# ws2803_top.net
KiCad netlist of a schematic drawn in EAGLE
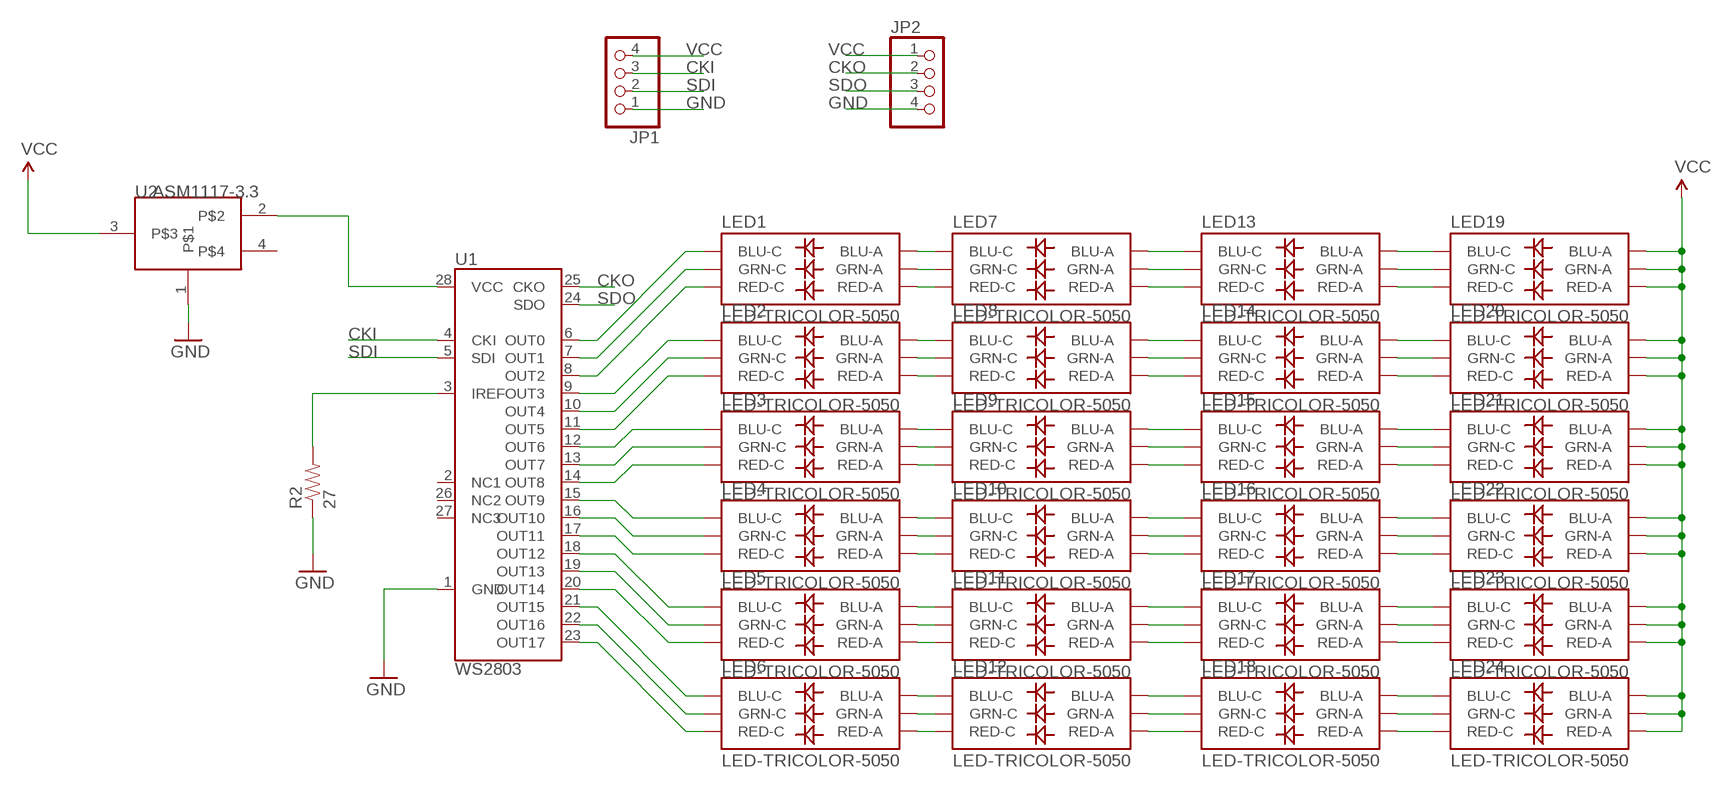
[diagram p0: schematic, sheet 1]

(export (version "E")
  (design (tool "Eeschema 10.0.6"))
  (components
    (comp (ref "JP1")
      (value "PINHD-1X4")
      (footprint "eagle-import:1X04")
      (libsource (lib "eagle-import") (part "PINHD-1X4"))
    )
    (comp (ref "JP2")
      (value "PINHD-1X4")
      (footprint "eagle-import:1X04")
      (libsource (lib "eagle-import") (part "PINHD-1X4"))
    )
    (comp (ref "LED1")
      (value "LED-TRICOLOR-5050")
      (footprint "eagle-import:LED-TRICOLOR-5050")
      (libsource (lib "eagle-import") (part "LED-TRICOLOR-5050"))
    )
    (comp (ref "LED2")
      (value "LED-TRICOLOR-5050")
      (footprint "eagle-import:LED-TRICOLOR-5050")
      (libsource (lib "eagle-import") (part "LED-TRICOLOR-5050"))
    )
    (comp (ref "LED3")
      (value "LED-TRICOLOR-5050")
      (footprint "eagle-import:LED-TRICOLOR-5050")
      (libsource (lib "eagle-import") (part "LED-TRICOLOR-5050"))
    )
    (comp (ref "LED4")
      (value "LED-TRICOLOR-5050")
      (footprint "eagle-import:LED-TRICOLOR-5050")
      (libsource (lib "eagle-import") (part "LED-TRICOLOR-5050"))
    )
    (comp (ref "LED5")
      (value "LED-TRICOLOR-5050")
      (footprint "eagle-import:LED-TRICOLOR-5050")
      (libsource (lib "eagle-import") (part "LED-TRICOLOR-5050"))
    )
    (comp (ref "LED6")
      (value "LED-TRICOLOR-5050")
      (footprint "eagle-import:LED-TRICOLOR-5050")
      (libsource (lib "eagle-import") (part "LED-TRICOLOR-5050"))
    )
    (comp (ref "LED7")
      (value "LED-TRICOLOR-5050")
      (footprint "eagle-import:LED-TRICOLOR-5050")
      (libsource (lib "eagle-import") (part "LED-TRICOLOR-5050"))
    )
    (comp (ref "LED8")
      (value "LED-TRICOLOR-5050")
      (footprint "eagle-import:LED-TRICOLOR-5050")
      (libsource (lib "eagle-import") (part "LED-TRICOLOR-5050"))
    )
    (comp (ref "LED9")
      (value "LED-TRICOLOR-5050")
      (footprint "eagle-import:LED-TRICOLOR-5050")
      (libsource (lib "eagle-import") (part "LED-TRICOLOR-5050"))
    )
    (comp (ref "LED10")
      (value "LED-TRICOLOR-5050")
      (footprint "eagle-import:LED-TRICOLOR-5050")
      (libsource (lib "eagle-import") (part "LED-TRICOLOR-5050"))
    )
    (comp (ref "LED11")
      (value "LED-TRICOLOR-5050")
      (footprint "eagle-import:LED-TRICOLOR-5050")
      (libsource (lib "eagle-import") (part "LED-TRICOLOR-5050"))
    )
    (comp (ref "LED12")
      (value "LED-TRICOLOR-5050")
      (footprint "eagle-import:LED-TRICOLOR-5050")
      (libsource (lib "eagle-import") (part "LED-TRICOLOR-5050"))
    )
    (comp (ref "LED13")
      (value "LED-TRICOLOR-5050")
      (footprint "eagle-import:LED-TRICOLOR-5050")
      (libsource (lib "eagle-import") (part "LED-TRICOLOR-5050"))
    )
    (comp (ref "LED14")
      (value "LED-TRICOLOR-5050")
      (footprint "eagle-import:LED-TRICOLOR-5050")
      (libsource (lib "eagle-import") (part "LED-TRICOLOR-5050"))
    )
    (comp (ref "LED15")
      (value "LED-TRICOLOR-5050")
      (footprint "eagle-import:LED-TRICOLOR-5050")
      (libsource (lib "eagle-import") (part "LED-TRICOLOR-5050"))
    )
    (comp (ref "LED16")
      (value "LED-TRICOLOR-5050")
      (footprint "eagle-import:LED-TRICOLOR-5050")
      (libsource (lib "eagle-import") (part "LED-TRICOLOR-5050"))
    )
    (comp (ref "LED17")
      (value "LED-TRICOLOR-5050")
      (footprint "eagle-import:LED-TRICOLOR-5050")
      (libsource (lib "eagle-import") (part "LED-TRICOLOR-5050"))
    )
    (comp (ref "LED18")
      (value "LED-TRICOLOR-5050")
      (footprint "eagle-import:LED-TRICOLOR-5050")
      (libsource (lib "eagle-import") (part "LED-TRICOLOR-5050"))
    )
    (comp (ref "LED19")
      (value "LED-TRICOLOR-5050")
      (footprint "eagle-import:LED-TRICOLOR-5050")
      (libsource (lib "eagle-import") (part "LED-TRICOLOR-5050"))
    )
    (comp (ref "LED20")
      (value "LED-TRICOLOR-5050")
      (footprint "eagle-import:LED-TRICOLOR-5050")
      (libsource (lib "eagle-import") (part "LED-TRICOLOR-5050"))
    )
    (comp (ref "LED21")
      (value "LED-TRICOLOR-5050")
      (footprint "eagle-import:LED-TRICOLOR-5050")
      (libsource (lib "eagle-import") (part "LED-TRICOLOR-5050"))
    )
    (comp (ref "LED22")
      (value "LED-TRICOLOR-5050")
      (footprint "eagle-import:LED-TRICOLOR-5050")
      (libsource (lib "eagle-import") (part "LED-TRICOLOR-5050"))
    )
    (comp (ref "LED23")
      (value "LED-TRICOLOR-5050")
      (footprint "eagle-import:LED-TRICOLOR-5050")
      (libsource (lib "eagle-import") (part "LED-TRICOLOR-5050"))
    )
    (comp (ref "LED24")
      (value "LED-TRICOLOR-5050")
      (footprint "eagle-import:LED-TRICOLOR-5050")
      (libsource (lib "eagle-import") (part "LED-TRICOLOR-5050"))
    )
    (comp (ref "R2")
      (value "27")
      (footprint "eagle-import:0603-RES")
      (libsource (lib "eagle-import") (part "RESISTOR0603-RES"))
    )
    (comp (ref "U1")
      (value "WS2803")
      (footprint "eagle-import:SOP-28")
      (libsource (lib "eagle-import") (part "WS2803"))
    )
    (comp (ref "U2")
      (value "ASM1117-3.3")
      (footprint "eagle-import:SOT223")
      (libsource (lib "eagle-import") (part "ASM1117-3.3"))
    )
  )
  (nets
    (net (code "1") (name "/CKI") (class "Default")
      (node (ref "JP1") (pin "3") (pinfunction "3_3") (pintype "passive"))
      (node (ref "U1") (pin "4") (pinfunction "CKI_4") (pintype "bidirectional"))
    )
    (net (code "2") (name "/CKO") (class "Default")
      (node (ref "JP2") (pin "2") (pinfunction "2_2") (pintype "passive"))
      (node (ref "U1") (pin "25") (pinfunction "CKO_25") (pintype "bidirectional"))
    )
    (net (code "3") (name "/SDI") (class "Default")
      (node (ref "JP1") (pin "2") (pinfunction "2_2") (pintype "passive"))
      (node (ref "U1") (pin "5") (pinfunction "SDI_5") (pintype "bidirectional"))
    )
    (net (code "4") (name "/SDO") (class "Default")
      (node (ref "JP2") (pin "3") (pinfunction "3_3") (pintype "passive"))
      (node (ref "U1") (pin "24") (pinfunction "SDO_24") (pintype "bidirectional"))
    )
    (net (code "5") (name "GND") (class "Default")
      (node (ref "JP1") (pin "1") (pinfunction "1_1") (pintype "passive"))
      (node (ref "JP2") (pin "4") (pinfunction "4_4") (pintype "passive"))
      (node (ref "R2") (pin "1") (pinfunction "1_1") (pintype "passive"))
      (node (ref "U1") (pin "1") (pinfunction "GND_1") (pintype "bidirectional"))
      (node (ref "U2") (pin "1") (pinfunction "P$1_1") (pintype "bidirectional"))
    )
    (net (code "6") (name "Net-(LED1-BLU-A)") (class "Default")
      (node (ref "LED1") (pin "3") (pinfunction "BLU-A_3") (pintype "bidirectional"))
      (node (ref "LED7") (pin "4") (pinfunction "BLU-C_4") (pintype "bidirectional"))
    )
    (net (code "7") (name "Net-(LED1-BLU-C)") (class "Default")
      (node (ref "LED1") (pin "4") (pinfunction "BLU-C_4") (pintype "bidirectional"))
      (node (ref "U1") (pin "6") (pinfunction "OUT0_6") (pintype "bidirectional"))
    )
    (net (code "8") (name "Net-(LED1-GRN-A)") (class "Default")
      (node (ref "LED1") (pin "1") (pinfunction "GRN-A_1") (pintype "bidirectional"))
      (node (ref "LED7") (pin "6") (pinfunction "GRN-C_6") (pintype "bidirectional"))
    )
    (net (code "9") (name "Net-(LED1-GRN-C)") (class "Default")
      (node (ref "LED1") (pin "6") (pinfunction "GRN-C_6") (pintype "bidirectional"))
      (node (ref "U1") (pin "7") (pinfunction "OUT1_7") (pintype "bidirectional"))
    )
    (net (code "10") (name "Net-(LED1-RED-A)") (class "Default")
      (node (ref "LED1") (pin "2") (pinfunction "RED-A_2") (pintype "bidirectional"))
      (node (ref "LED7") (pin "5") (pinfunction "RED-C_5") (pintype "bidirectional"))
    )
    (net (code "11") (name "Net-(LED1-RED-C)") (class "Default")
      (node (ref "LED1") (pin "5") (pinfunction "RED-C_5") (pintype "bidirectional"))
      (node (ref "U1") (pin "8") (pinfunction "OUT2_8") (pintype "bidirectional"))
    )
    (net (code "12") (name "Net-(LED2-BLU-A)") (class "Default")
      (node (ref "LED2") (pin "3") (pinfunction "BLU-A_3") (pintype "bidirectional"))
      (node (ref "LED8") (pin "4") (pinfunction "BLU-C_4") (pintype "bidirectional"))
    )
    (net (code "13") (name "Net-(LED2-BLU-C)") (class "Default")
      (node (ref "LED2") (pin "4") (pinfunction "BLU-C_4") (pintype "bidirectional"))
      (node (ref "U1") (pin "9") (pinfunction "OUT3_9") (pintype "bidirectional"))
    )
    (net (code "14") (name "Net-(LED2-GRN-A)") (class "Default")
      (node (ref "LED2") (pin "1") (pinfunction "GRN-A_1") (pintype "bidirectional"))
      (node (ref "LED8") (pin "6") (pinfunction "GRN-C_6") (pintype "bidirectional"))
    )
    (net (code "15") (name "Net-(LED2-GRN-C)") (class "Default")
      (node (ref "LED2") (pin "6") (pinfunction "GRN-C_6") (pintype "bidirectional"))
      (node (ref "U1") (pin "10") (pinfunction "OUT4_10") (pintype "bidirectional"))
    )
    (net (code "16") (name "Net-(LED2-RED-A)") (class "Default")
      (node (ref "LED2") (pin "2") (pinfunction "RED-A_2") (pintype "bidirectional"))
      (node (ref "LED8") (pin "5") (pinfunction "RED-C_5") (pintype "bidirectional"))
    )
    (net (code "17") (name "Net-(LED2-RED-C)") (class "Default")
      (node (ref "LED2") (pin "5") (pinfunction "RED-C_5") (pintype "bidirectional"))
      (node (ref "U1") (pin "11") (pinfunction "OUT5_11") (pintype "bidirectional"))
    )
    (net (code "18") (name "Net-(LED3-BLU-A)") (class "Default")
      (node (ref "LED3") (pin "3") (pinfunction "BLU-A_3") (pintype "bidirectional"))
      (node (ref "LED9") (pin "4") (pinfunction "BLU-C_4") (pintype "bidirectional"))
    )
    (net (code "19") (name "Net-(LED3-BLU-C)") (class "Default")
      (node (ref "LED3") (pin "4") (pinfunction "BLU-C_4") (pintype "bidirectional"))
      (node (ref "U1") (pin "12") (pinfunction "OUT6_12") (pintype "bidirectional"))
    )
    (net (code "20") (name "Net-(LED3-GRN-A)") (class "Default")
      (node (ref "LED3") (pin "1") (pinfunction "GRN-A_1") (pintype "bidirectional"))
      (node (ref "LED9") (pin "6") (pinfunction "GRN-C_6") (pintype "bidirectional"))
    )
    (net (code "21") (name "Net-(LED3-GRN-C)") (class "Default")
      (node (ref "LED3") (pin "6") (pinfunction "GRN-C_6") (pintype "bidirectional"))
      (node (ref "U1") (pin "13") (pinfunction "OUT7_13") (pintype "bidirectional"))
    )
    (net (code "22") (name "Net-(LED3-RED-A)") (class "Default")
      (node (ref "LED3") (pin "2") (pinfunction "RED-A_2") (pintype "bidirectional"))
      (node (ref "LED9") (pin "5") (pinfunction "RED-C_5") (pintype "bidirectional"))
    )
    (net (code "23") (name "Net-(LED3-RED-C)") (class "Default")
      (node (ref "LED3") (pin "5") (pinfunction "RED-C_5") (pintype "bidirectional"))
      (node (ref "U1") (pin "14") (pinfunction "OUT8_14") (pintype "bidirectional"))
    )
    (net (code "24") (name "Net-(LED4-BLU-C)") (class "Default")
      (node (ref "LED4") (pin "4") (pinfunction "BLU-C_4") (pintype "bidirectional"))
      (node (ref "U1") (pin "15") (pinfunction "OUT9_15") (pintype "bidirectional"))
    )
    (net (code "25") (name "Net-(LED4-GRN-C)") (class "Default")
      (node (ref "LED4") (pin "6") (pinfunction "GRN-C_6") (pintype "bidirectional"))
      (node (ref "U1") (pin "16") (pinfunction "OUT10_16") (pintype "bidirectional"))
    )
    (net (code "26") (name "Net-(LED4-RED-C)") (class "Default")
      (node (ref "LED4") (pin "5") (pinfunction "RED-C_5") (pintype "bidirectional"))
      (node (ref "U1") (pin "17") (pinfunction "OUT11_17") (pintype "bidirectional"))
    )
    (net (code "27") (name "Net-(LED5-BLU-C)") (class "Default")
      (node (ref "LED5") (pin "4") (pinfunction "BLU-C_4") (pintype "bidirectional"))
      (node (ref "U1") (pin "18") (pinfunction "OUT12_18") (pintype "bidirectional"))
    )
    (net (code "28") (name "Net-(LED5-GRN-C)") (class "Default")
      (node (ref "LED5") (pin "6") (pinfunction "GRN-C_6") (pintype "bidirectional"))
      (node (ref "U1") (pin "19") (pinfunction "OUT13_19") (pintype "bidirectional"))
    )
    (net (code "29") (name "Net-(LED5-RED-C)") (class "Default")
      (node (ref "LED5") (pin "5") (pinfunction "RED-C_5") (pintype "bidirectional"))
      (node (ref "U1") (pin "20") (pinfunction "OUT14_20") (pintype "bidirectional"))
    )
    (net (code "30") (name "Net-(LED6-BLU-C)") (class "Default")
      (node (ref "LED6") (pin "4") (pinfunction "BLU-C_4") (pintype "bidirectional"))
      (node (ref "U1") (pin "21") (pinfunction "OUT15_21") (pintype "bidirectional"))
    )
    (net (code "31") (name "Net-(LED6-GRN-C)") (class "Default")
      (node (ref "LED6") (pin "6") (pinfunction "GRN-C_6") (pintype "bidirectional"))
      (node (ref "U1") (pin "22") (pinfunction "OUT16_22") (pintype "bidirectional"))
    )
    (net (code "32") (name "Net-(LED6-RED-C)") (class "Default")
      (node (ref "LED6") (pin "5") (pinfunction "RED-C_5") (pintype "bidirectional"))
      (node (ref "U1") (pin "23") (pinfunction "OUT17_23") (pintype "bidirectional"))
    )
    (net (code "33") (name "Net-(LED10-BLU-A)") (class "Default")
      (node (ref "LED10") (pin "3") (pinfunction "BLU-A_3") (pintype "bidirectional"))
      (node (ref "LED16") (pin "4") (pinfunction "BLU-C_4") (pintype "bidirectional"))
    )
    (net (code "34") (name "Net-(LED10-BLU-C)") (class "Default")
      (node (ref "LED10") (pin "4") (pinfunction "BLU-C_4") (pintype "bidirectional"))
      (node (ref "LED4") (pin "3") (pinfunction "BLU-A_3") (pintype "bidirectional"))
    )
    (net (code "35") (name "Net-(LED10-GRN-A)") (class "Default")
      (node (ref "LED10") (pin "1") (pinfunction "GRN-A_1") (pintype "bidirectional"))
      (node (ref "LED16") (pin "6") (pinfunction "GRN-C_6") (pintype "bidirectional"))
    )
    (net (code "36") (name "Net-(LED10-GRN-C)") (class "Default")
      (node (ref "LED10") (pin "6") (pinfunction "GRN-C_6") (pintype "bidirectional"))
      (node (ref "LED4") (pin "1") (pinfunction "GRN-A_1") (pintype "bidirectional"))
    )
    (net (code "37") (name "Net-(LED10-RED-A)") (class "Default")
      (node (ref "LED10") (pin "2") (pinfunction "RED-A_2") (pintype "bidirectional"))
      (node (ref "LED16") (pin "5") (pinfunction "RED-C_5") (pintype "bidirectional"))
    )
    (net (code "38") (name "Net-(LED10-RED-C)") (class "Default")
      (node (ref "LED10") (pin "5") (pinfunction "RED-C_5") (pintype "bidirectional"))
      (node (ref "LED4") (pin "2") (pinfunction "RED-A_2") (pintype "bidirectional"))
    )
    (net (code "39") (name "Net-(LED11-BLU-A)") (class "Default")
      (node (ref "LED11") (pin "3") (pinfunction "BLU-A_3") (pintype "bidirectional"))
      (node (ref "LED17") (pin "4") (pinfunction "BLU-C_4") (pintype "bidirectional"))
    )
    (net (code "40") (name "Net-(LED11-BLU-C)") (class "Default")
      (node (ref "LED11") (pin "4") (pinfunction "BLU-C_4") (pintype "bidirectional"))
      (node (ref "LED5") (pin "3") (pinfunction "BLU-A_3") (pintype "bidirectional"))
    )
    (net (code "41") (name "Net-(LED11-GRN-A)") (class "Default")
      (node (ref "LED11") (pin "1") (pinfunction "GRN-A_1") (pintype "bidirectional"))
      (node (ref "LED17") (pin "6") (pinfunction "GRN-C_6") (pintype "bidirectional"))
    )
    (net (code "42") (name "Net-(LED11-GRN-C)") (class "Default")
      (node (ref "LED11") (pin "6") (pinfunction "GRN-C_6") (pintype "bidirectional"))
      (node (ref "LED5") (pin "1") (pinfunction "GRN-A_1") (pintype "bidirectional"))
    )
    (net (code "43") (name "Net-(LED11-RED-A)") (class "Default")
      (node (ref "LED11") (pin "2") (pinfunction "RED-A_2") (pintype "bidirectional"))
      (node (ref "LED17") (pin "5") (pinfunction "RED-C_5") (pintype "bidirectional"))
    )
    (net (code "44") (name "Net-(LED11-RED-C)") (class "Default")
      (node (ref "LED11") (pin "5") (pinfunction "RED-C_5") (pintype "bidirectional"))
      (node (ref "LED5") (pin "2") (pinfunction "RED-A_2") (pintype "bidirectional"))
    )
    (net (code "45") (name "Net-(LED12-BLU-A)") (class "Default")
      (node (ref "LED12") (pin "3") (pinfunction "BLU-A_3") (pintype "bidirectional"))
      (node (ref "LED18") (pin "4") (pinfunction "BLU-C_4") (pintype "bidirectional"))
    )
    (net (code "46") (name "Net-(LED12-BLU-C)") (class "Default")
      (node (ref "LED12") (pin "4") (pinfunction "BLU-C_4") (pintype "bidirectional"))
      (node (ref "LED6") (pin "3") (pinfunction "BLU-A_3") (pintype "bidirectional"))
    )
    (net (code "47") (name "Net-(LED12-GRN-A)") (class "Default")
      (node (ref "LED12") (pin "1") (pinfunction "GRN-A_1") (pintype "bidirectional"))
      (node (ref "LED18") (pin "6") (pinfunction "GRN-C_6") (pintype "bidirectional"))
    )
    (net (code "48") (name "Net-(LED12-GRN-C)") (class "Default")
      (node (ref "LED12") (pin "6") (pinfunction "GRN-C_6") (pintype "bidirectional"))
      (node (ref "LED6") (pin "1") (pinfunction "GRN-A_1") (pintype "bidirectional"))
    )
    (net (code "49") (name "Net-(LED12-RED-A)") (class "Default")
      (node (ref "LED12") (pin "2") (pinfunction "RED-A_2") (pintype "bidirectional"))
      (node (ref "LED18") (pin "5") (pinfunction "RED-C_5") (pintype "bidirectional"))
    )
    (net (code "50") (name "Net-(LED12-RED-C)") (class "Default")
      (node (ref "LED12") (pin "5") (pinfunction "RED-C_5") (pintype "bidirectional"))
      (node (ref "LED6") (pin "2") (pinfunction "RED-A_2") (pintype "bidirectional"))
    )
    (net (code "51") (name "Net-(LED13-BLU-A)") (class "Default")
      (node (ref "LED13") (pin "3") (pinfunction "BLU-A_3") (pintype "bidirectional"))
      (node (ref "LED19") (pin "4") (pinfunction "BLU-C_4") (pintype "bidirectional"))
    )
    (net (code "52") (name "Net-(LED13-BLU-C)") (class "Default")
      (node (ref "LED13") (pin "4") (pinfunction "BLU-C_4") (pintype "bidirectional"))
      (node (ref "LED7") (pin "3") (pinfunction "BLU-A_3") (pintype "bidirectional"))
    )
    (net (code "53") (name "Net-(LED13-GRN-A)") (class "Default")
      (node (ref "LED13") (pin "1") (pinfunction "GRN-A_1") (pintype "bidirectional"))
      (node (ref "LED19") (pin "6") (pinfunction "GRN-C_6") (pintype "bidirectional"))
    )
    (net (code "54") (name "Net-(LED13-GRN-C)") (class "Default")
      (node (ref "LED13") (pin "6") (pinfunction "GRN-C_6") (pintype "bidirectional"))
      (node (ref "LED7") (pin "1") (pinfunction "GRN-A_1") (pintype "bidirectional"))
    )
    (net (code "55") (name "Net-(LED13-RED-A)") (class "Default")
      (node (ref "LED13") (pin "2") (pinfunction "RED-A_2") (pintype "bidirectional"))
      (node (ref "LED19") (pin "5") (pinfunction "RED-C_5") (pintype "bidirectional"))
    )
    (net (code "56") (name "Net-(LED13-RED-C)") (class "Default")
      (node (ref "LED13") (pin "5") (pinfunction "RED-C_5") (pintype "bidirectional"))
      (node (ref "LED7") (pin "2") (pinfunction "RED-A_2") (pintype "bidirectional"))
    )
    (net (code "57") (name "Net-(LED14-BLU-A)") (class "Default")
      (node (ref "LED14") (pin "3") (pinfunction "BLU-A_3") (pintype "bidirectional"))
      (node (ref "LED20") (pin "4") (pinfunction "BLU-C_4") (pintype "bidirectional"))
    )
    (net (code "58") (name "Net-(LED14-BLU-C)") (class "Default")
      (node (ref "LED14") (pin "4") (pinfunction "BLU-C_4") (pintype "bidirectional"))
      (node (ref "LED8") (pin "3") (pinfunction "BLU-A_3") (pintype "bidirectional"))
    )
    (net (code "59") (name "Net-(LED14-GRN-A)") (class "Default")
      (node (ref "LED14") (pin "1") (pinfunction "GRN-A_1") (pintype "bidirectional"))
      (node (ref "LED20") (pin "6") (pinfunction "GRN-C_6") (pintype "bidirectional"))
    )
    (net (code "60") (name "Net-(LED14-GRN-C)") (class "Default")
      (node (ref "LED14") (pin "6") (pinfunction "GRN-C_6") (pintype "bidirectional"))
      (node (ref "LED8") (pin "1") (pinfunction "GRN-A_1") (pintype "bidirectional"))
    )
    (net (code "61") (name "Net-(LED14-RED-A)") (class "Default")
      (node (ref "LED14") (pin "2") (pinfunction "RED-A_2") (pintype "bidirectional"))
      (node (ref "LED20") (pin "5") (pinfunction "RED-C_5") (pintype "bidirectional"))
    )
    (net (code "62") (name "Net-(LED14-RED-C)") (class "Default")
      (node (ref "LED14") (pin "5") (pinfunction "RED-C_5") (pintype "bidirectional"))
      (node (ref "LED8") (pin "2") (pinfunction "RED-A_2") (pintype "bidirectional"))
    )
    (net (code "63") (name "Net-(LED15-BLU-A)") (class "Default")
      (node (ref "LED15") (pin "3") (pinfunction "BLU-A_3") (pintype "bidirectional"))
      (node (ref "LED21") (pin "4") (pinfunction "BLU-C_4") (pintype "bidirectional"))
    )
    (net (code "64") (name "Net-(LED15-BLU-C)") (class "Default")
      (node (ref "LED15") (pin "4") (pinfunction "BLU-C_4") (pintype "bidirectional"))
      (node (ref "LED9") (pin "3") (pinfunction "BLU-A_3") (pintype "bidirectional"))
    )
    (net (code "65") (name "Net-(LED15-GRN-A)") (class "Default")
      (node (ref "LED15") (pin "1") (pinfunction "GRN-A_1") (pintype "bidirectional"))
      (node (ref "LED21") (pin "6") (pinfunction "GRN-C_6") (pintype "bidirectional"))
    )
    (net (code "66") (name "Net-(LED15-GRN-C)") (class "Default")
      (node (ref "LED15") (pin "6") (pinfunction "GRN-C_6") (pintype "bidirectional"))
      (node (ref "LED9") (pin "1") (pinfunction "GRN-A_1") (pintype "bidirectional"))
    )
    (net (code "67") (name "Net-(LED15-RED-A)") (class "Default")
      (node (ref "LED15") (pin "2") (pinfunction "RED-A_2") (pintype "bidirectional"))
      (node (ref "LED21") (pin "5") (pinfunction "RED-C_5") (pintype "bidirectional"))
    )
    (net (code "68") (name "Net-(LED15-RED-C)") (class "Default")
      (node (ref "LED15") (pin "5") (pinfunction "RED-C_5") (pintype "bidirectional"))
      (node (ref "LED9") (pin "2") (pinfunction "RED-A_2") (pintype "bidirectional"))
    )
    (net (code "69") (name "Net-(LED16-BLU-A)") (class "Default")
      (node (ref "LED16") (pin "3") (pinfunction "BLU-A_3") (pintype "bidirectional"))
      (node (ref "LED22") (pin "4") (pinfunction "BLU-C_4") (pintype "bidirectional"))
    )
    (net (code "70") (name "Net-(LED16-GRN-A)") (class "Default")
      (node (ref "LED16") (pin "1") (pinfunction "GRN-A_1") (pintype "bidirectional"))
      (node (ref "LED22") (pin "6") (pinfunction "GRN-C_6") (pintype "bidirectional"))
    )
    (net (code "71") (name "Net-(LED16-RED-A)") (class "Default")
      (node (ref "LED16") (pin "2") (pinfunction "RED-A_2") (pintype "bidirectional"))
      (node (ref "LED22") (pin "5") (pinfunction "RED-C_5") (pintype "bidirectional"))
    )
    (net (code "72") (name "Net-(LED17-BLU-A)") (class "Default")
      (node (ref "LED17") (pin "3") (pinfunction "BLU-A_3") (pintype "bidirectional"))
      (node (ref "LED23") (pin "4") (pinfunction "BLU-C_4") (pintype "bidirectional"))
    )
    (net (code "73") (name "Net-(LED17-GRN-A)") (class "Default")
      (node (ref "LED17") (pin "1") (pinfunction "GRN-A_1") (pintype "bidirectional"))
      (node (ref "LED23") (pin "6") (pinfunction "GRN-C_6") (pintype "bidirectional"))
    )
    (net (code "74") (name "Net-(LED17-RED-A)") (class "Default")
      (node (ref "LED17") (pin "2") (pinfunction "RED-A_2") (pintype "bidirectional"))
      (node (ref "LED23") (pin "5") (pinfunction "RED-C_5") (pintype "bidirectional"))
    )
    (net (code "75") (name "Net-(LED18-BLU-A)") (class "Default")
      (node (ref "LED18") (pin "3") (pinfunction "BLU-A_3") (pintype "bidirectional"))
      (node (ref "LED24") (pin "4") (pinfunction "BLU-C_4") (pintype "bidirectional"))
    )
    (net (code "76") (name "Net-(LED18-GRN-A)") (class "Default")
      (node (ref "LED18") (pin "1") (pinfunction "GRN-A_1") (pintype "bidirectional"))
      (node (ref "LED24") (pin "6") (pinfunction "GRN-C_6") (pintype "bidirectional"))
    )
    (net (code "77") (name "Net-(LED18-RED-A)") (class "Default")
      (node (ref "LED18") (pin "2") (pinfunction "RED-A_2") (pintype "bidirectional"))
      (node (ref "LED24") (pin "5") (pinfunction "RED-C_5") (pintype "bidirectional"))
    )
    (net (code "78") (name "Net-(U1-IREF)") (class "Default")
      (node (ref "R2") (pin "2") (pinfunction "2_2") (pintype "passive"))
      (node (ref "U1") (pin "3") (pinfunction "IREF_3") (pintype "bidirectional"))
    )
    (net (code "79") (name "Net-(U1-VCC)") (class "Default")
      (node (ref "U1") (pin "28") (pinfunction "VCC_28") (pintype "bidirectional"))
      (node (ref "U2") (pin "2") (pinfunction "P$2_2") (pintype "bidirectional"))
    )
    (net (code "80") (name "VCC") (class "Default")
      (node (ref "JP1") (pin "4") (pinfunction "4_4") (pintype "passive"))
      (node (ref "JP2") (pin "1") (pinfunction "1_1") (pintype "passive"))
      (node (ref "LED19") (pin "1") (pinfunction "GRN-A_1") (pintype "bidirectional"))
      (node (ref "LED19") (pin "2") (pinfunction "RED-A_2") (pintype "bidirectional"))
      (node (ref "LED19") (pin "3") (pinfunction "BLU-A_3") (pintype "bidirectional"))
      (node (ref "LED20") (pin "1") (pinfunction "GRN-A_1") (pintype "bidirectional"))
      (node (ref "LED20") (pin "2") (pinfunction "RED-A_2") (pintype "bidirectional"))
      (node (ref "LED20") (pin "3") (pinfunction "BLU-A_3") (pintype "bidirectional"))
      (node (ref "LED21") (pin "1") (pinfunction "GRN-A_1") (pintype "bidirectional"))
      (node (ref "LED21") (pin "2") (pinfunction "RED-A_2") (pintype "bidirectional"))
      (node (ref "LED21") (pin "3") (pinfunction "BLU-A_3") (pintype "bidirectional"))
      (node (ref "LED22") (pin "1") (pinfunction "GRN-A_1") (pintype "bidirectional"))
      (node (ref "LED22") (pin "2") (pinfunction "RED-A_2") (pintype "bidirectional"))
      (node (ref "LED22") (pin "3") (pinfunction "BLU-A_3") (pintype "bidirectional"))
      (node (ref "LED23") (pin "1") (pinfunction "GRN-A_1") (pintype "bidirectional"))
      (node (ref "LED23") (pin "2") (pinfunction "RED-A_2") (pintype "bidirectional"))
      (node (ref "LED23") (pin "3") (pinfunction "BLU-A_3") (pintype "bidirectional"))
      (node (ref "LED24") (pin "1") (pinfunction "GRN-A_1") (pintype "bidirectional"))
      (node (ref "LED24") (pin "2") (pinfunction "RED-A_2") (pintype "bidirectional"))
      (node (ref "LED24") (pin "3") (pinfunction "BLU-A_3") (pintype "bidirectional"))
      (node (ref "U2") (pin "3") (pinfunction "P$3_3") (pintype "bidirectional"))
    )
    (net (code "81") (name "unconnected-(U1-NC1-Pad2)") (class "Default")
      (node (ref "U1") (pin "2") (pinfunction "NC1_2") (pintype "bidirectional"))
    )
    (net (code "82") (name "unconnected-(U1-NC2-Pad26)") (class "Default")
      (node (ref "U1") (pin "26") (pinfunction "NC2_26") (pintype "bidirectional"))
    )
    (net (code "83") (name "unconnected-(U1-NC3-Pad27)") (class "Default")
      (node (ref "U1") (pin "27") (pinfunction "NC3_27") (pintype "bidirectional"))
    )
    (net (code "84") (name "unconnected-(U2-P$4-Pad4)") (class "Default")
      (node (ref "U2") (pin "4") (pinfunction "P$4_4") (pintype "bidirectional"))
    )
  )
)
